# RELAY10.net
KiCad netlist of a schematic drawn in Altium Designer
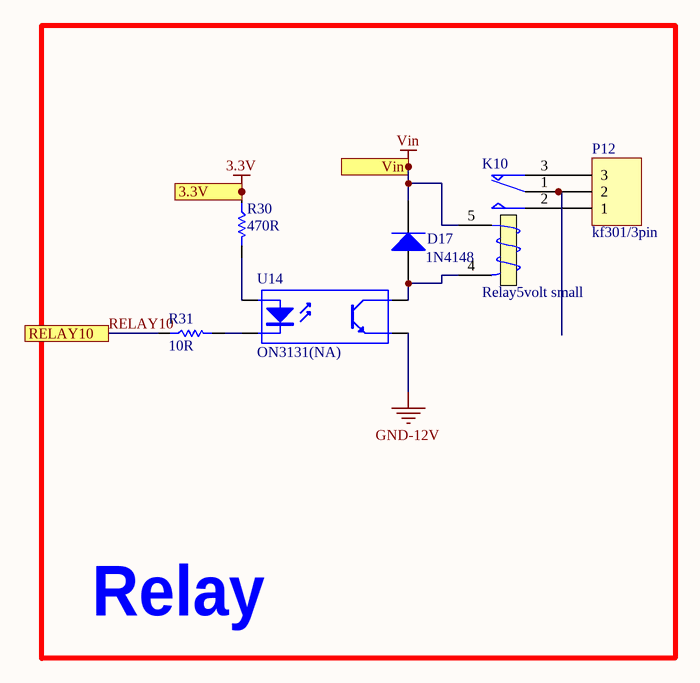
[diagram p0: RELAY10.SchDoc]

(export (version "E")
  (design (tool "Eeschema 10.0.6"))
  (components
    (comp (ref "D17")
      (value "1N4148")
      (footprint "sod123")
      (description "1 Amp General Purpose Rectifier")
      (fields (field (name "PUBLISHER") "Altium Limited"))
      (libsource (lib "Miscellaneous Devices") (part "Diode 1N4007"))
    )
    (comp (ref "K10")
      (value "Relay5volt small")
      (footprint "relay5_childern")
      (description "SPDT Relay")
      (fields (field (name "PUBLISHER") "Altium Limited"))
      (libsource (lib "FLIB") (part "Relay"))
    )
    (comp (ref "P12")
      (value "kf301/3pin")
      (footprint "Blue Connector 1*3 -kf301")
      (fields (field (name "PUBLISHER") "Altium Limited"))
      (libsource (lib "Miscellaneous Connectors") (part "Header 3"))
    )
    (comp (ref "R30")
      (value "470R")
      (footprint "0805/resistor")
      (description "Resistor")
      (fields (field (name "TOLERANCE") "5%") (field (name "POWER") "1/8 W"))
      (libsource (lib "skille") (part "Resistor"))
    )
    (comp (ref "R31")
      (value "10R")
      (footprint "0805/resistor")
      (description "Resistor")
      (fields (field (name "TOLERANCE") "5%") (field (name "POWER") "1/8 W"))
      (libsource (lib "skille") (part "Resistor"))
    )
    (comp (ref "U14")
      (value "ON3131(NA)")
      (footprint "OPTO_COUPLER")
      (description "4-Pin Phototransistor Optocoupler")
      (fields (field (name "PUBLISHER") "Altium Limited"))
      (libsource (lib "skille") (part "Optoisolator1"))
    )
  )
  (nets
    (net (code "1") (name "/RELAY10") (class "Default")
      (node (ref "R31") (pin "1") (pinfunction "1_1") (pintype "passive"))
    )
    (net (code "2") (name "3.3V") (class "Default")
      (node (ref "R30") (pin "1") (pinfunction "1_1") (pintype "passive"))
    )
    (net (code "3") (name "GND-12V") (class "Default")
      (node (ref "U14") (pin "3") (pinfunction "E_3") (pintype "passive"))
    )
    (net (code "4") (name "Net-(K10-COM)") (class "Default")
      (node (ref "K10") (pin "1") (pinfunction "COM_1") (pintype "passive"))
      (node (ref "P12") (pin "2") (pinfunction "2_2") (pintype "passive"))
    )
    (net (code "5") (name "Net-(K10-NO)") (class "Default")
      (node (ref "K10") (pin "2") (pinfunction "NO_2") (pintype "passive"))
      (node (ref "P12") (pin "1") (pinfunction "1_1") (pintype "passive"))
    )
    (net (code "6") (name "Net-(K10-T1)") (class "Default")
      (node (ref "K10") (pin "3") (pinfunction "T1_3") (pintype "passive"))
      (node (ref "P12") (pin "3") (pinfunction "3_3") (pintype "passive"))
    )
    (net (code "7") (name "Net-(K10-T2)") (class "Default")
      (node (ref "D17") (pin "A") (pinfunction "A_A") (pintype "passive"))
      (node (ref "K10") (pin "4") (pinfunction "T2_4") (pintype "passive"))
      (node (ref "U14") (pin "4") (pinfunction "C_4") (pintype "passive"))
    )
    (net (code "8") (name "Net-(U14-A)") (class "Default")
      (node (ref "R30") (pin "2") (pinfunction "2_2") (pintype "passive"))
      (node (ref "U14") (pin "1") (pinfunction "A_1") (pintype "passive"))
    )
    (net (code "9") (name "Net-(U14-K)") (class "Default")
      (node (ref "R31") (pin "2") (pinfunction "2_2") (pintype "passive"))
      (node (ref "U14") (pin "2") (pinfunction "K_2") (pintype "passive"))
    )
    (net (code "10") (name "Vin") (class "Default")
      (node (ref "D17") (pin "K") (pinfunction "K_K") (pintype "passive"))
      (node (ref "K10") (pin "5") (pinfunction "5_5") (pintype "passive"))
    )
  )
)
